# ProProject_ssd1306_2024-04-10.net
KiCad netlist of a schematic drawn in EasyEDA Pro
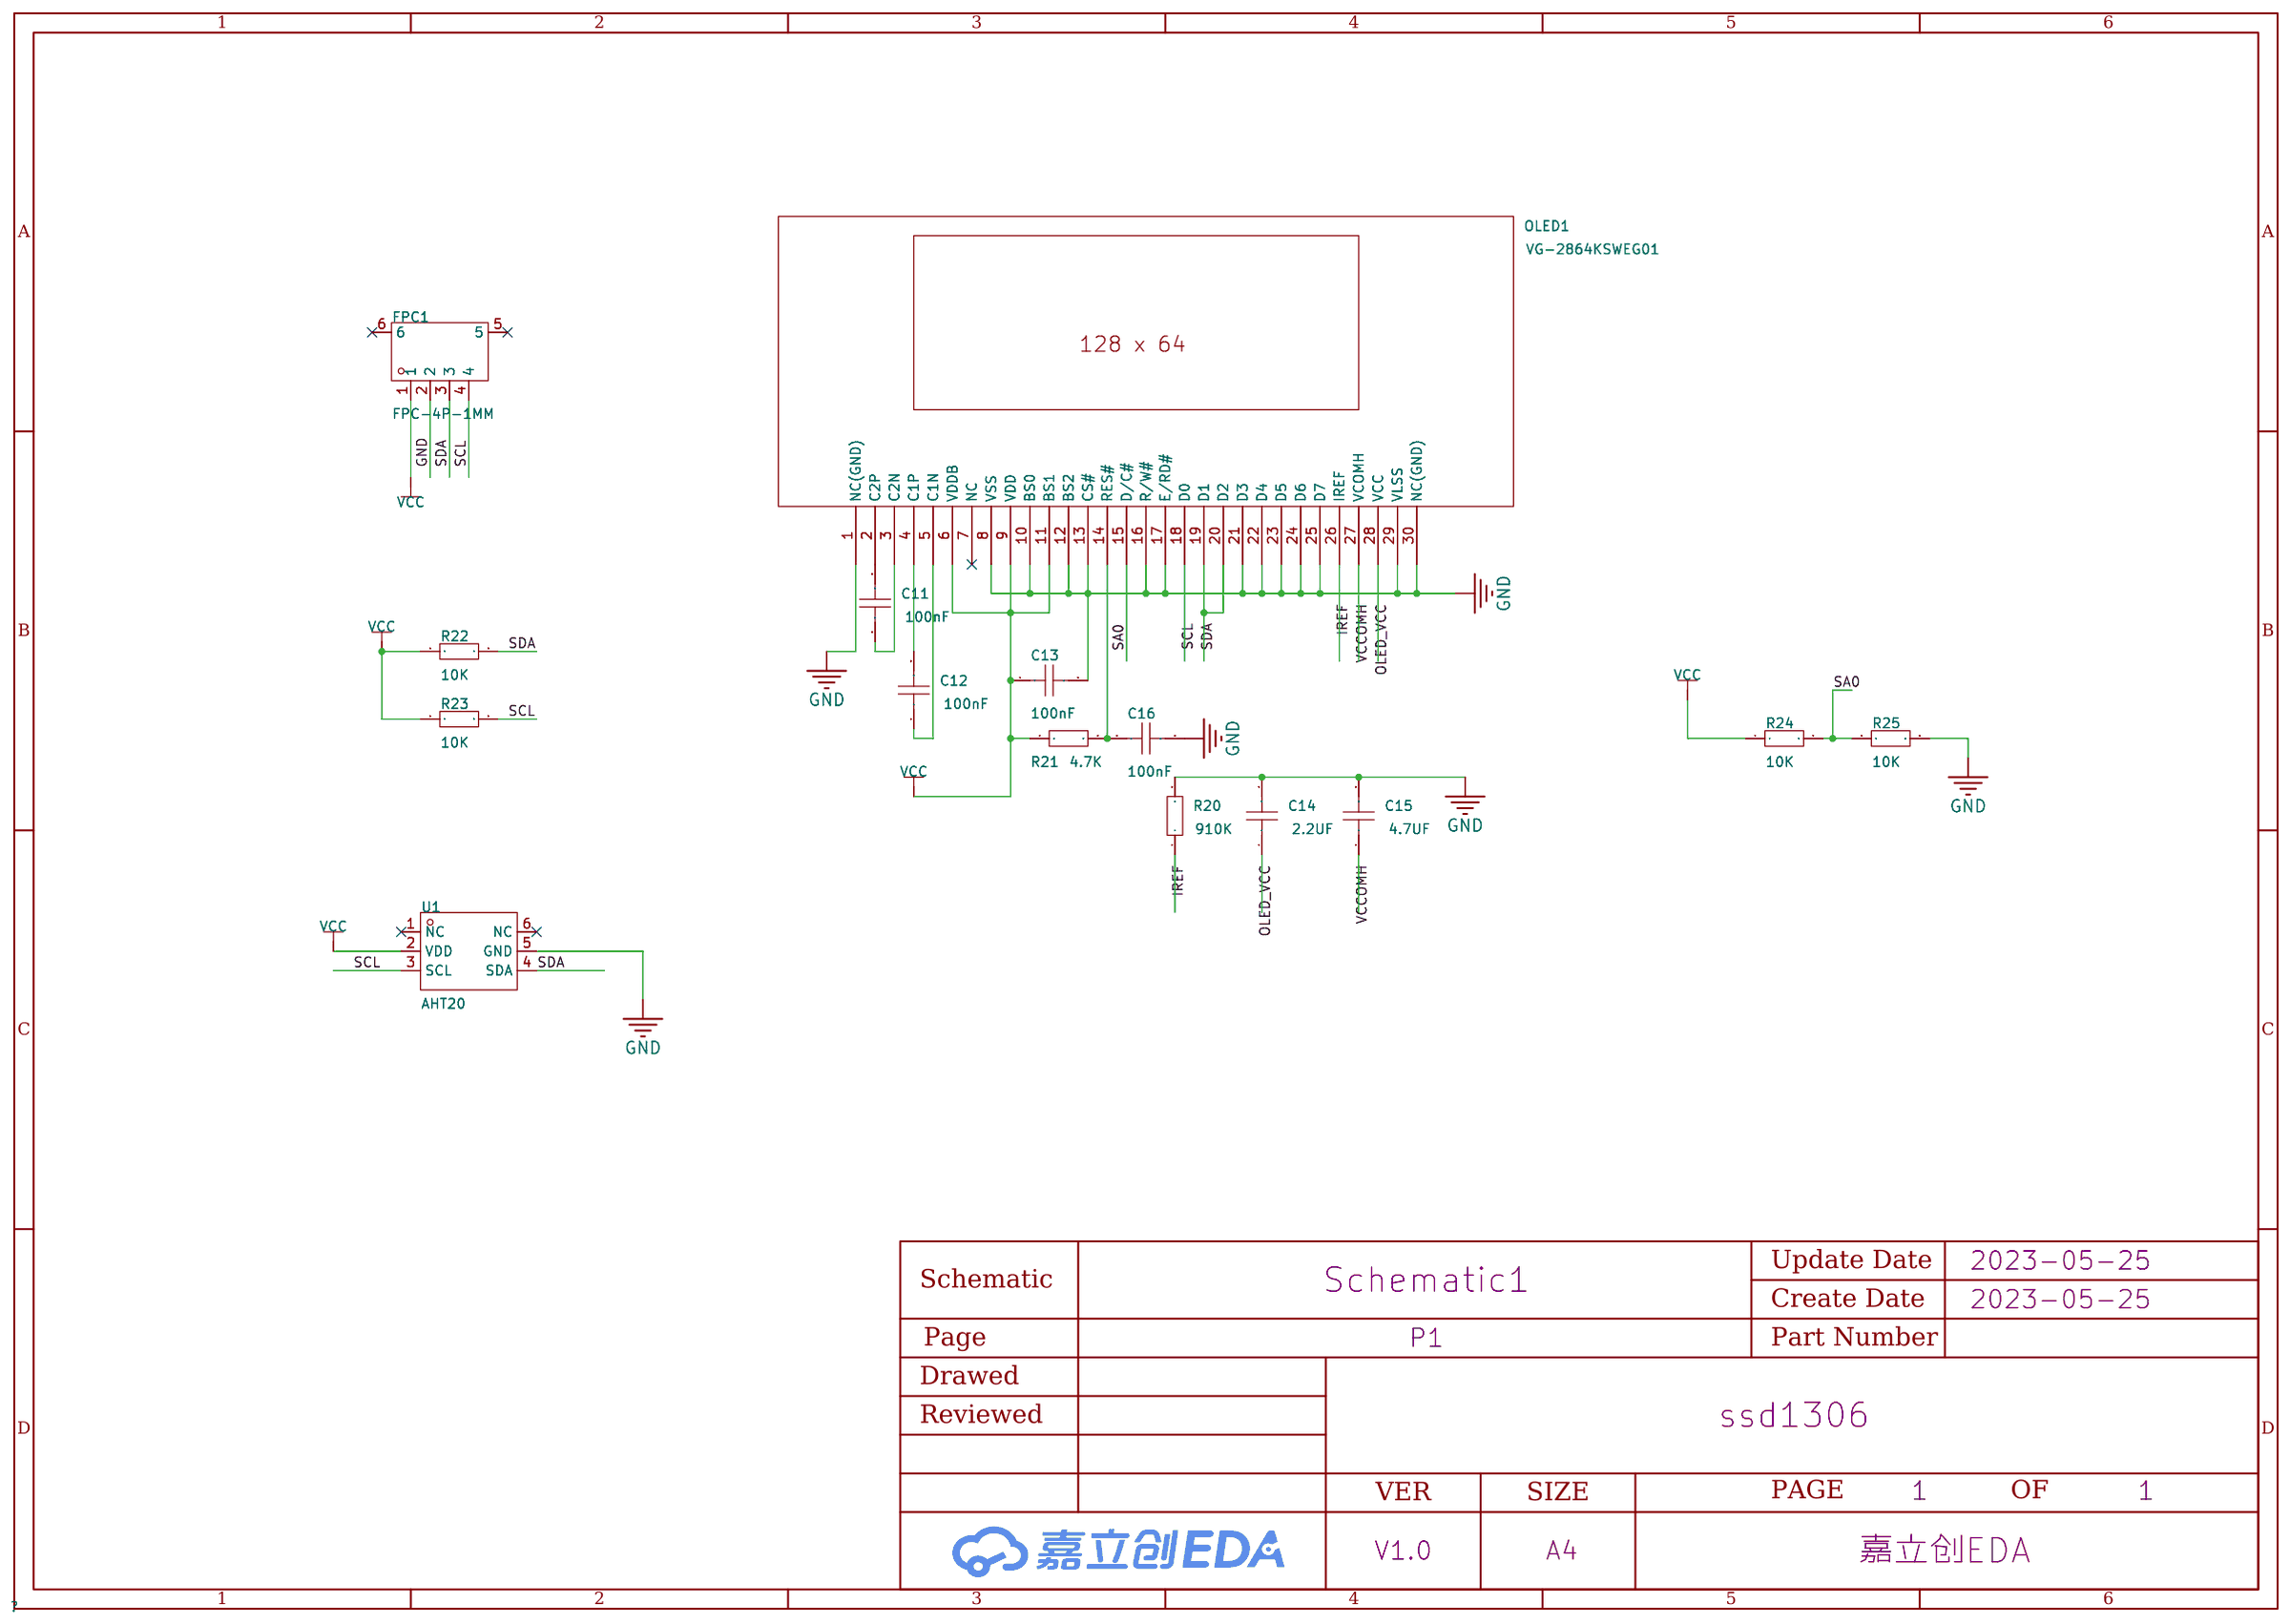
[diagram p0: schematic sheet]

(export (version "E")
  (design (tool "Eeschema 10.0.6"))
  (components
    (comp (ref "C11")
      (value "100nF")
      (footprint "easyedapro:C0603")
      (libsource (lib "easyedapro") (part "CapAcitance"))
    )
    (comp (ref "C12")
      (value "100nF")
      (footprint "easyedapro:C0603")
      (libsource (lib "easyedapro") (part "CapAcitance"))
    )
    (comp (ref "C13")
      (value "100nF")
      (footprint "easyedapro:C0603")
      (libsource (lib "easyedapro") (part "CapAcitance"))
    )
    (comp (ref "C14")
      (value "2.2UF")
      (footprint "easyedapro:C0603")
      (libsource (lib "easyedapro") (part "CapAcitance"))
    )
    (comp (ref "C15")
      (value "4.7UF")
      (footprint "easyedapro:C0603")
      (libsource (lib "easyedapro") (part "CapAcitance"))
    )
    (comp (ref "C16")
      (value "100nF")
      (footprint "easyedapro:C0603")
      (libsource (lib "easyedapro") (part "CapAcitance"))
    )
    (comp (ref "FPC1")
      (value "FPC-4P-1MM")
      (footprint "easyedapro:FFC-SMD_FFC10032-04SBB123W5M")
      (description "间距:1mm;触点数量:4;锁定特性:翻盖式;安装类型:卧贴;触点类型:下接;工作温度范围:-25°C~+85°C;")
      (fields (field (name "Manufacturer") "TXGA(特思嘉)"))
      (libsource (lib "easyedapro") (part "FFC10032-04SBB123W5M"))
    )
    (comp (ref "OLED1")
      (value "VG-2864KSWEG01")
      (footprint "easyedapro:OLED_0.96-30P-P0.70-12864")
      (description "尺寸(inch):0.96;主控芯片:SSD1306;")
      (fields (field (name "Manufacturer") "WiseChip(智晶光电)"))
      (libsource (lib "easyedapro") (part "VG-2864KSWEG01"))
    )
    (comp (ref "R20")
      (value "910K")
      (footprint "easyedapro:R0603")
      (libsource (lib "easyedapro") (part "电阻"))
    )
    (comp (ref "R21")
      (value "4.7K")
      (footprint "easyedapro:R0603")
      (libsource (lib "easyedapro") (part "电阻"))
    )
    (comp (ref "R22") (value "10K") (footprint "easyedapro:R0603") (libsource (lib "easyedapro") (part "电阻")))
    (comp (ref "R23") (value "10K") (footprint "easyedapro:R0603") (libsource (lib "easyedapro") (part "电阻")))
    (comp (ref "R24") (value "10K") (footprint "easyedapro:R0603") (libsource (lib "easyedapro") (part "电阻")))
    (comp (ref "R25") (value "10K") (footprint "easyedapro:R0603") (libsource (lib "easyedapro") (part "电阻")))
    (comp (ref "U1")
      (value "AHT20")
      (footprint "easyedapro:SENSOR-SMD_L3.0-W3.0-P1.00-BR")
      (fields (field (name "Manufacturer") "广州奥松"))
      (libsource (lib "easyedapro") (part "AHT20_C2757850"))
    )
  )
  (nets
    (net (code "1") (name "/IREF") (class "Default")
      (node (ref "OLED1") (pin "26") (pinfunction "IREF_26") (pintype "input"))
      (node (ref "R20") (pin "1") (pinfunction "1_1") (pintype "input"))
    )
    (net (code "2") (name "/OLED_VCC") (class "Default")
      (node (ref "C14") (pin "1") (pinfunction "1_1") (pintype "input"))
      (node (ref "OLED1") (pin "28") (pinfunction "VCC_28") (pintype "input"))
    )
    (net (code "3") (name "/SA0") (class "Default")
      (node (ref "OLED1") (pin "15") (pinfunction "D/C#_15") (pintype "input"))
      (node (ref "R24") (pin "2") (pinfunction "2_2") (pintype "input"))
      (node (ref "R25") (pin "1") (pinfunction "1_1") (pintype "input"))
    )
    (net (code "4") (name "/SCL") (class "Default")
      (node (ref "FPC1") (pin "4") (pinfunction "4_4") (pintype "input"))
      (node (ref "OLED1") (pin "18") (pinfunction "D0_18") (pintype "input"))
      (node (ref "R23") (pin "2") (pinfunction "2_2") (pintype "input"))
      (node (ref "U1") (pin "3") (pinfunction "SCL_3") (pintype "unspecified"))
    )
    (net (code "5") (name "/SDA") (class "Default")
      (node (ref "FPC1") (pin "3") (pinfunction "3_3") (pintype "input"))
      (node (ref "OLED1") (pin "19") (pinfunction "D1_19") (pintype "input"))
      (node (ref "OLED1") (pin "20") (pinfunction "D2_20") (pintype "input"))
      (node (ref "R22") (pin "2") (pinfunction "2_2") (pintype "input"))
      (node (ref "U1") (pin "4") (pinfunction "SDA_4") (pintype "unspecified"))
    )
    (net (code "6") (name "/VCCOMH") (class "Default")
      (node (ref "C15") (pin "1") (pinfunction "1_1") (pintype "input"))
      (node (ref "OLED1") (pin "27") (pinfunction "VCOMH_27") (pintype "input"))
    )
    (net (code "7") (name "GND") (class "Default")
      (node (ref "C13") (pin "2") (pinfunction "2_2") (pintype "input"))
      (node (ref "C14") (pin "2") (pinfunction "2_2") (pintype "input"))
      (node (ref "C15") (pin "2") (pinfunction "2_2") (pintype "input"))
      (node (ref "C16") (pin "2") (pinfunction "2_2") (pintype "input"))
      (node (ref "FPC1") (pin "2") (pinfunction "2_2") (pintype "input"))
      (node (ref "OLED1") (pin "1") (pinfunction "NC(GND)_1") (pintype "input"))
      (node (ref "OLED1") (pin "10") (pinfunction "BS0_10") (pintype "input"))
      (node (ref "OLED1") (pin "12") (pinfunction "BS2_12") (pintype "input"))
      (node (ref "OLED1") (pin "13") (pinfunction "CS#_13") (pintype "input"))
      (node (ref "OLED1") (pin "16") (pinfunction "R/W#_16") (pintype "input"))
      (node (ref "OLED1") (pin "17") (pinfunction "E/RD#_17") (pintype "input"))
      (node (ref "OLED1") (pin "21") (pinfunction "D3_21") (pintype "input"))
      (node (ref "OLED1") (pin "22") (pinfunction "D4_22") (pintype "input"))
      (node (ref "OLED1") (pin "23") (pinfunction "D5_23") (pintype "input"))
      (node (ref "OLED1") (pin "24") (pinfunction "D6_24") (pintype "input"))
      (node (ref "OLED1") (pin "25") (pinfunction "D7_25") (pintype "input"))
      (node (ref "OLED1") (pin "29") (pinfunction "VLSS_29") (pintype "input"))
      (node (ref "OLED1") (pin "30") (pinfunction "NC(GND)_30") (pintype "input"))
      (node (ref "OLED1") (pin "8") (pinfunction "VSS_8") (pintype "input"))
      (node (ref "R20") (pin "2") (pinfunction "2_2") (pintype "input"))
      (node (ref "R25") (pin "2") (pinfunction "2_2") (pintype "input"))
      (node (ref "U1") (pin "5") (pinfunction "GND_5") (pintype "unspecified"))
    )
    (net (code "8") (name "Net-(OLED1-C1N)") (class "Default")
      (node (ref "C12") (pin "1") (pinfunction "1_1") (pintype "input"))
      (node (ref "OLED1") (pin "5") (pinfunction "C1N_5") (pintype "input"))
    )
    (net (code "9") (name "Net-(OLED1-C1P)") (class "Default")
      (node (ref "C12") (pin "2") (pinfunction "2_2") (pintype "input"))
      (node (ref "OLED1") (pin "4") (pinfunction "C1P_4") (pintype "input"))
    )
    (net (code "10") (name "Net-(OLED1-C2N)") (class "Default")
      (node (ref "C11") (pin "1") (pinfunction "1_1") (pintype "input"))
      (node (ref "OLED1") (pin "3") (pinfunction "C2N_3") (pintype "input"))
    )
    (net (code "11") (name "Net-(OLED1-C2P)") (class "Default")
      (node (ref "C11") (pin "2") (pinfunction "2_2") (pintype "input"))
      (node (ref "OLED1") (pin "2") (pinfunction "C2P_2") (pintype "input"))
    )
    (net (code "12") (name "Net-(OLED1-RES#)") (class "Default")
      (node (ref "C16") (pin "1") (pinfunction "1_1") (pintype "input"))
      (node (ref "OLED1") (pin "14") (pinfunction "RES#_14") (pintype "input"))
      (node (ref "R21") (pin "2") (pinfunction "2_2") (pintype "input"))
    )
    (net (code "13") (name "VCC") (class "Default")
      (node (ref "C13") (pin "1") (pinfunction "1_1") (pintype "input"))
      (node (ref "FPC1") (pin "1") (pinfunction "1_1") (pintype "input"))
      (node (ref "OLED1") (pin "11") (pinfunction "BS1_11") (pintype "input"))
      (node (ref "OLED1") (pin "6") (pinfunction "VDDB_6") (pintype "input"))
      (node (ref "OLED1") (pin "9") (pinfunction "VDD_9") (pintype "input"))
      (node (ref "R21") (pin "1") (pinfunction "1_1") (pintype "input"))
      (node (ref "R22") (pin "1") (pinfunction "1_1") (pintype "input"))
      (node (ref "R23") (pin "1") (pinfunction "1_1") (pintype "input"))
      (node (ref "R24") (pin "1") (pinfunction "1_1") (pintype "input"))
      (node (ref "U1") (pin "2") (pinfunction "VDD_2") (pintype "unspecified"))
    )
    (net (code "14") (name "unconnected-(FPC1-Pad5)") (class "Default")
      (node (ref "FPC1") (pin "5") (pinfunction "5_5") (pintype "input+no_connect"))
    )
    (net (code "15") (name "unconnected-(FPC1-Pad6)") (class "Default")
      (node (ref "FPC1") (pin "6") (pinfunction "6_6") (pintype "input+no_connect"))
    )
    (net (code "16") (name "unconnected-(OLED1-NC-Pad7)") (class "Default")
      (node (ref "OLED1") (pin "7") (pinfunction "NC_7") (pintype "input+no_connect"))
    )
    (net (code "17") (name "unconnected-(U1-NC-Pad1)") (class "Default")
      (node (ref "U1") (pin "1") (pinfunction "NC_1") (pintype "unspecified+no_connect"))
    )
    (net (code "18") (name "unconnected-(U1-NC-Pad6)") (class "Default")
      (node (ref "U1") (pin "6") (pinfunction "NC_6") (pintype "unspecified+no_connect"))
    )
  )
)
